# BBB_CNC.net
KiCad netlist of a schematic drawn in EAGLE
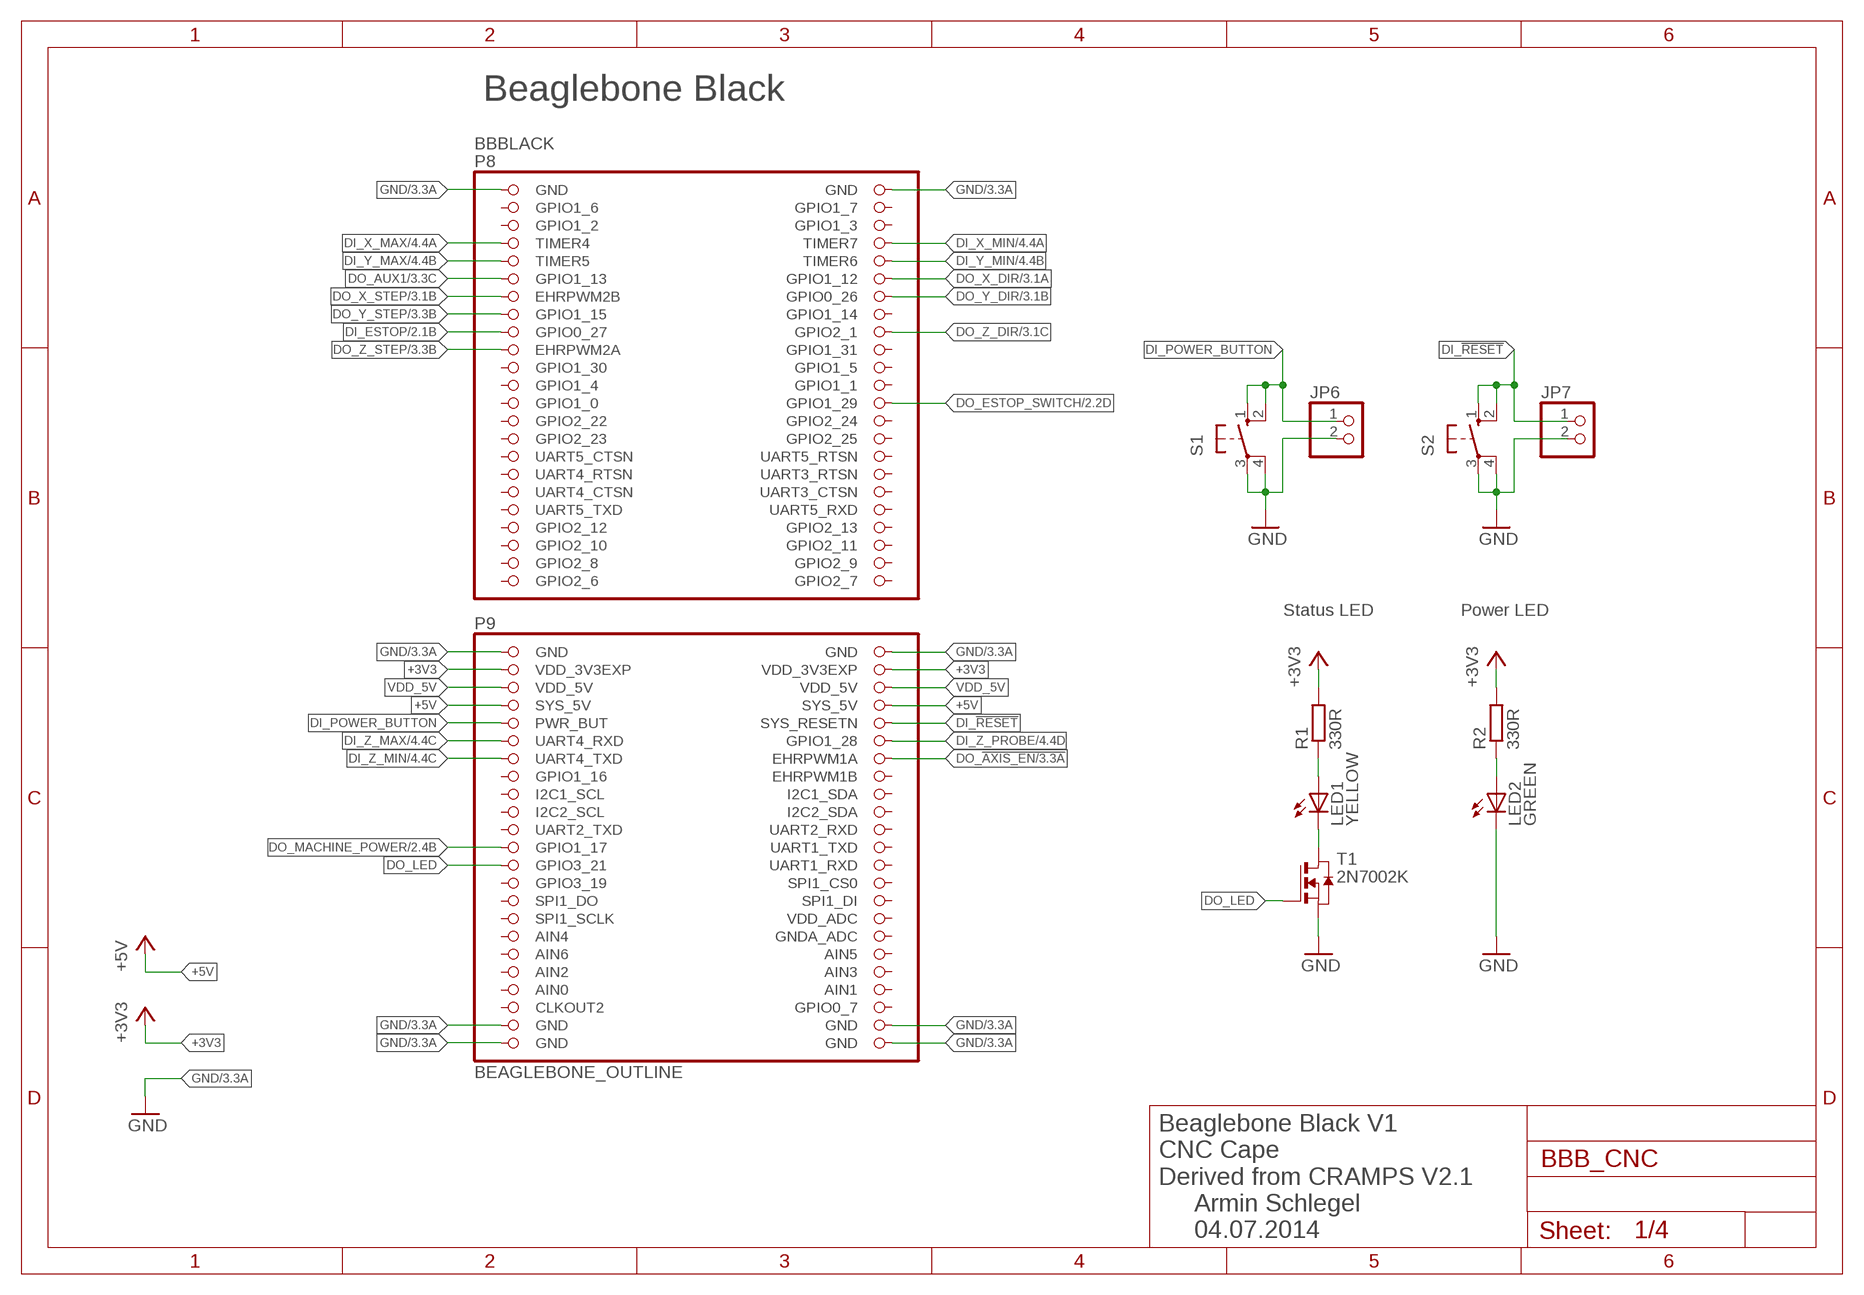
[diagram p0: schematic, sheet 1]
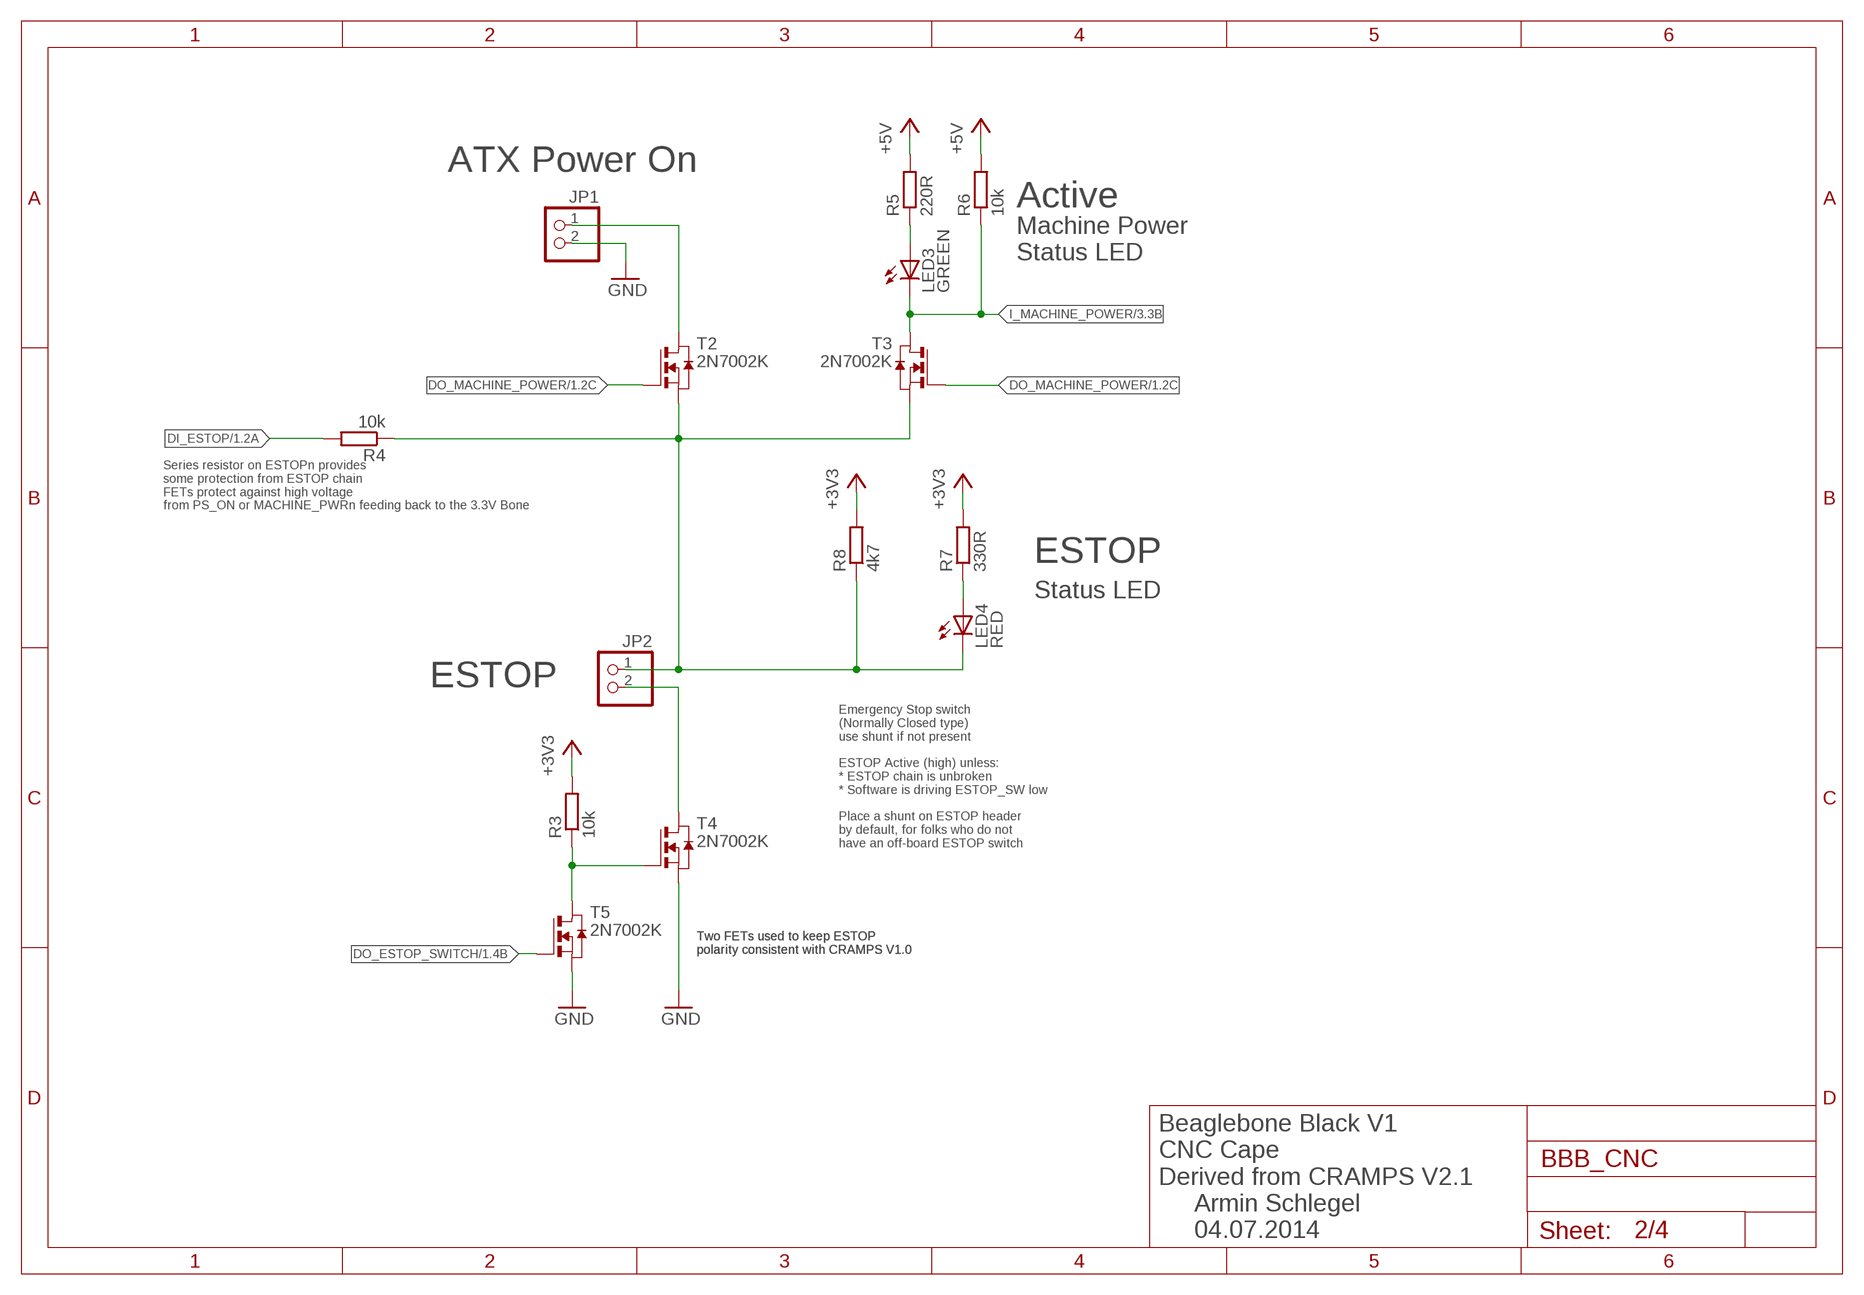
[diagram p1: schematic, sheet 2]
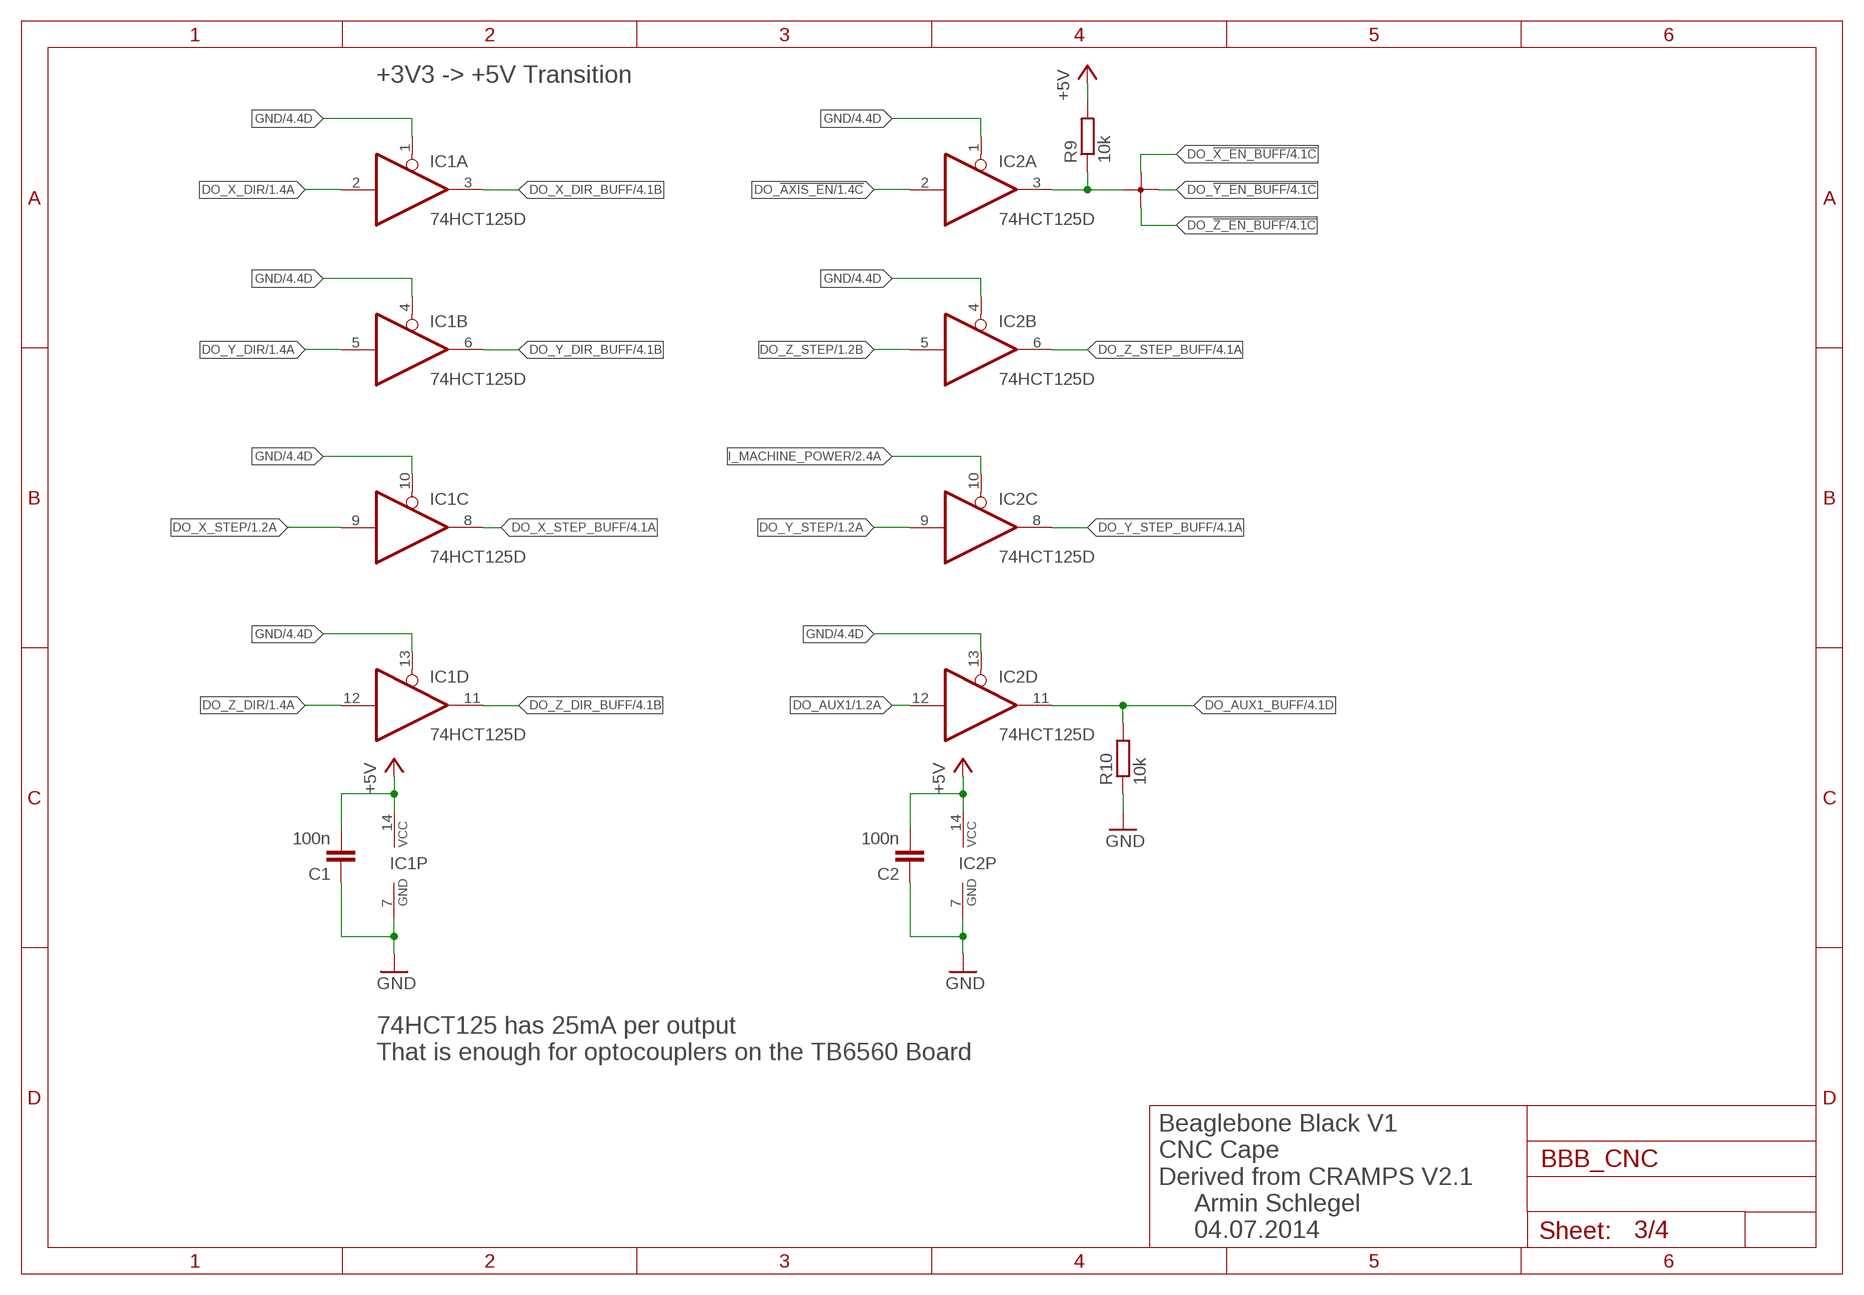
[diagram p2: schematic, sheet 3]
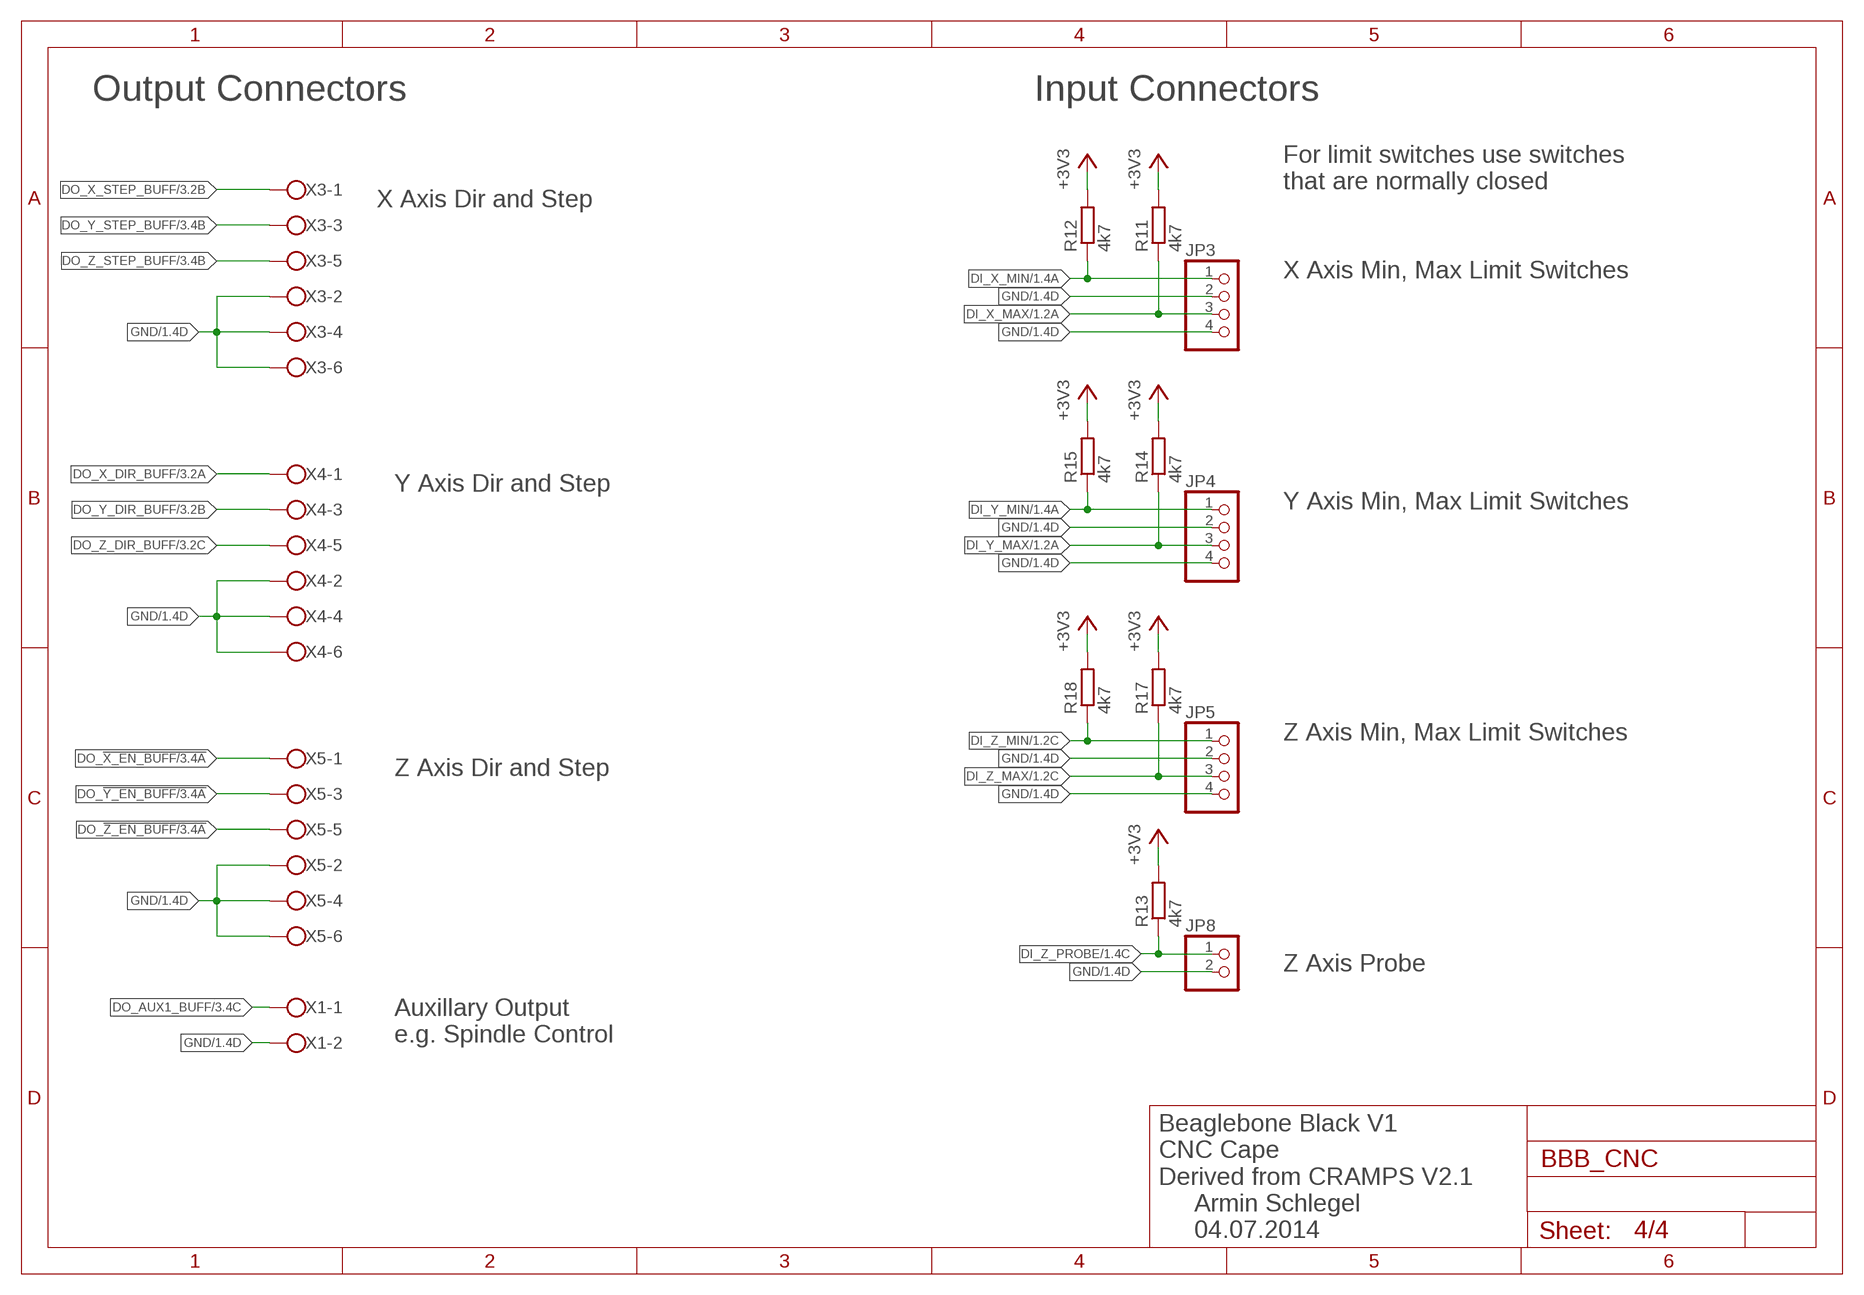
[diagram p3: schematic, sheet 4]

(export (version "E")
  (design (tool "Eeschema 10.0.6"))
  (components
    (comp (ref "JP1")
      (value "PINHD-1X2")
      (footprint "eagle-import:1X02")
      (libsource (lib "eagle-import") (part "PINHD-1X2"))
    )
    (comp (ref "JP2")
      (value "PINHD-1X2")
      (footprint "eagle-import:1X02")
      (libsource (lib "eagle-import") (part "PINHD-1X2"))
    )
    (comp (ref "LED3")
      (value "GREEN")
      (footprint "eagle-import:SML0805")
      (libsource (lib "eagle-import") (part "LEDSML0805"))
    )
    (comp (ref "LED4")
      (value "RED")
      (footprint "eagle-import:SML0805")
      (libsource (lib "eagle-import") (part "LEDSML0805"))
    )
    (comp (ref "R3")
      (value "10k")
      (footprint "eagle-import:R0603")
      (libsource (lib "eagle-import") (part "R-EU_R0603"))
    )
    (comp (ref "R4")
      (value "10k")
      (footprint "eagle-import:R0603")
      (libsource (lib "eagle-import") (part "R-EU_R0603"))
    )
    (comp (ref "R5")
      (value "220R")
      (footprint "eagle-import:R0603")
      (libsource (lib "eagle-import") (part "R-EU_R0603"))
    )
    (comp (ref "R6")
      (value "10k")
      (footprint "eagle-import:R0603")
      (libsource (lib "eagle-import") (part "R-EU_R0603"))
    )
    (comp (ref "R7")
      (value "330R")
      (footprint "eagle-import:R0603")
      (libsource (lib "eagle-import") (part "R-EU_R0603"))
    )
    (comp (ref "R8")
      (value "4k7")
      (footprint "eagle-import:R0603")
      (libsource (lib "eagle-import") (part "R-EU_R0603"))
    )
    (comp (ref "T2")
      (value "2N7002K")
      (footprint "eagle-import:SOT-23")
      (libsource (lib "eagle-import") (part "NMOSSOT23"))
    )
    (comp (ref "T3")
      (value "2N7002K")
      (footprint "eagle-import:SOT-23")
      (libsource (lib "eagle-import") (part "NMOSSOT23"))
    )
    (comp (ref "T4")
      (value "2N7002K")
      (footprint "eagle-import:SOT-23")
      (libsource (lib "eagle-import") (part "NMOSSOT23"))
    )
    (comp (ref "T5")
      (value "2N7002K")
      (footprint "eagle-import:SOT-23")
      (libsource (lib "eagle-import") (part "NMOSSOT23"))
    )
    (comp (ref "JP3")
      (value "PINHD-1X4")
      (footprint "eagle-import:1X04")
      (libsource (lib "eagle-import") (part "PINHD-1X4"))
    )
    (comp (ref "JP4")
      (value "PINHD-1X4")
      (footprint "eagle-import:1X04")
      (libsource (lib "eagle-import") (part "PINHD-1X4"))
    )
    (comp (ref "JP5")
      (value "PINHD-1X4")
      (footprint "eagle-import:1X04")
      (libsource (lib "eagle-import") (part "PINHD-1X4"))
    )
    (comp (ref "JP8")
      (value "PINHD-1X2")
      (footprint "eagle-import:1X02")
      (libsource (lib "eagle-import") (part "PINHD-1X2"))
    )
    (comp (ref "R11")
      (value "4k7")
      (footprint "eagle-import:R0603")
      (libsource (lib "eagle-import") (part "R-EU_R0603"))
    )
    (comp (ref "R12")
      (value "4k7")
      (footprint "eagle-import:R0603")
      (libsource (lib "eagle-import") (part "R-EU_R0603"))
    )
    (comp (ref "R13")
      (value "4k7")
      (footprint "eagle-import:R0603")
      (libsource (lib "eagle-import") (part "R-EU_R0603"))
    )
    (comp (ref "R14")
      (value "4k7")
      (footprint "eagle-import:R0603")
      (libsource (lib "eagle-import") (part "R-EU_R0603"))
    )
    (comp (ref "R15")
      (value "4k7")
      (footprint "eagle-import:R0603")
      (libsource (lib "eagle-import") (part "R-EU_R0603"))
    )
    (comp (ref "R17")
      (value "4k7")
      (footprint "eagle-import:R0603")
      (libsource (lib "eagle-import") (part "R-EU_R0603"))
    )
    (comp (ref "R18")
      (value "4k7")
      (footprint "eagle-import:R0603")
      (libsource (lib "eagle-import") (part "R-EU_R0603"))
    )
    (comp (ref "X1")
      (value "W237-102")
      (footprint "eagle-import:W237-102")
      (fields (field (name "MPN") "237-102"))
      (libsource (lib "eagle-import") (part "W237-102"))
    )
    (comp (ref "X3")
      (value "W237-136")
      (footprint "eagle-import:W237-136")
      (fields (field (name "MPN") "237-136"))
      (libsource (lib "eagle-import") (part "W237-136"))
    )
    (comp (ref "X4")
      (value "W237-136")
      (footprint "eagle-import:W237-136")
      (fields (field (name "MPN") "237-136"))
      (libsource (lib "eagle-import") (part "W237-136"))
    )
    (comp (ref "X5")
      (value "W237-136")
      (footprint "eagle-import:W237-136")
      (fields (field (name "MPN") "237-136"))
      (libsource (lib "eagle-import") (part "W237-136"))
    )
    (comp (ref "BBBLACK")
      (value "BEAGLEBONE_OUTLINE")
      (footprint "eagle-import:BEAGLEBONE_SHIELD")
      (libsource (lib "eagle-import") (part "BEAGLEBONE_OUTLINE"))
    )
    (comp (ref "JP6")
      (value "PINHD-1X2")
      (footprint "eagle-import:1X02")
      (libsource (lib "eagle-import") (part "PINHD-1X2"))
    )
    (comp (ref "JP7")
      (value "PINHD-1X2")
      (footprint "eagle-import:1X02")
      (libsource (lib "eagle-import") (part "PINHD-1X2"))
    )
    (comp (ref "LED1")
      (value "YELLOW")
      (footprint "eagle-import:SML0805")
      (libsource (lib "eagle-import") (part "LEDSML0805"))
    )
    (comp (ref "LED2")
      (value "GREEN")
      (footprint "eagle-import:SML0805")
      (libsource (lib "eagle-import") (part "LEDSML0805"))
    )
    (comp (ref "R1")
      (value "330R")
      (footprint "eagle-import:R0603")
      (libsource (lib "eagle-import") (part "R-EU_R0603"))
    )
    (comp (ref "R2")
      (value "330R")
      (footprint "eagle-import:R0603")
      (libsource (lib "eagle-import") (part "R-EU_R0603"))
    )
    (comp (ref "S1")
      (value "10-XX")
      (footprint "eagle-import:B3F-10XX")
      (fields (field (name "MPN") "B3F-1000"))
      (libsource (lib "eagle-import") (part "10-XX"))
    )
    (comp (ref "S2")
      (value "10-XX")
      (footprint "eagle-import:B3F-10XX")
      (fields (field (name "MPN") "B3F-1000"))
      (libsource (lib "eagle-import") (part "10-XX"))
    )
    (comp (ref "T1")
      (value "2N7002K")
      (footprint "eagle-import:SOT-23")
      (libsource (lib "eagle-import") (part "NMOSSOT23"))
    )
    (comp (ref "C1")
      (value "100n")
      (footprint "eagle-import:C0603K")
      (libsource (lib "eagle-import") (part "C-EUC0603K"))
    )
    (comp (ref "C2")
      (value "100n")
      (footprint "eagle-import:C0603K")
      (libsource (lib "eagle-import") (part "C-EUC0603K"))
    )
    (comp (ref "IC1")
      (value "74HCT125D")
      (footprint "eagle-import:SO14")
      (libsource (lib "eagle-import") (part "74125DHCT"))
    )
    (comp (ref "IC2")
      (value "74HCT125D")
      (footprint "eagle-import:SO14")
      (libsource (lib "eagle-import") (part "74125DHCT"))
    )
    (comp (ref "R9")
      (value "10k")
      (footprint "eagle-import:R0603")
      (libsource (lib "eagle-import") (part "R-EU_R0603"))
    )
    (comp (ref "R10")
      (value "10k")
      (footprint "eagle-import:R0603")
      (libsource (lib "eagle-import") (part "R-EU_R0603"))
    )
    (comp (ref "SP1")
      (value "SP4")
      (footprint "eagle-import:SP4")
      (libsource (lib "eagle-import") (part "SP4"))
    )
  )
  (nets
    (net (code "1") (name "+3V3") (class "Default")
      (node (ref "BBBLACK") (pin "49") (pinfunction "VDD_3V3EXP_49") (pintype "power_in"))
      (node (ref "BBBLACK") (pin "50") (pinfunction "VDD_3V3EXP_50") (pintype "power_in"))
      (node (ref "R1") (pin "2") (pinfunction "2_2") (pintype "passive"))
      (node (ref "R11") (pin "2") (pinfunction "2_2") (pintype "passive"))
      (node (ref "R12") (pin "2") (pinfunction "2_2") (pintype "passive"))
      (node (ref "R13") (pin "2") (pinfunction "2_2") (pintype "passive"))
      (node (ref "R14") (pin "2") (pinfunction "2_2") (pintype "passive"))
      (node (ref "R15") (pin "2") (pinfunction "2_2") (pintype "passive"))
      (node (ref "R17") (pin "2") (pinfunction "2_2") (pintype "passive"))
      (node (ref "R18") (pin "2") (pinfunction "2_2") (pintype "passive"))
      (node (ref "R2") (pin "2") (pinfunction "2_2") (pintype "passive"))
      (node (ref "R3") (pin "2") (pinfunction "2_2") (pintype "passive"))
      (node (ref "R7") (pin "2") (pinfunction "2_2") (pintype "passive"))
      (node (ref "R8") (pin "2") (pinfunction "2_2") (pintype "passive"))
    )
    (net (code "2") (name "+5V") (class "Default")
      (node (ref "BBBLACK") (pin "53") (pinfunction "SYS_5V_53") (pintype "power_in"))
      (node (ref "BBBLACK") (pin "54") (pinfunction "SYS_5V_54") (pintype "passive"))
      (node (ref "C1") (pin "2") (pinfunction "2_2") (pintype "passive"))
      (node (ref "C2") (pin "2") (pinfunction "2_2") (pintype "passive"))
      (node (ref "IC1") (pin "14") (pinfunction "VCC_14") (pintype "power_in"))
      (node (ref "IC2") (pin "14") (pinfunction "VCC_14") (pintype "power_in"))
      (node (ref "R5") (pin "2") (pinfunction "2_2") (pintype "passive"))
      (node (ref "R6") (pin "2") (pinfunction "2_2") (pintype "passive"))
      (node (ref "R9") (pin "2") (pinfunction "2_2") (pintype "passive"))
    )
    (net (code "3") (name "AIN0") (class "Default")
      (node (ref "BBBLACK") (pin "85") (pinfunction "AIN0_85") (pintype "power_in"))
    )
    (net (code "4") (name "DI_ESTOP") (class "Default")
      (node (ref "BBBLACK") (pin "17") (pinfunction "GPIO0_27_17") (pintype "passive"))
      (node (ref "R4") (pin "2") (pinfunction "2_2") (pintype "passive"))
    )
    (net (code "5") (name "DI_POWER_BUTTON") (class "Default")
      (node (ref "BBBLACK") (pin "55") (pinfunction "PWR_BUT_55") (pintype "passive"))
      (node (ref "JP6") (pin "1") (pinfunction "1_1") (pintype "passive"))
      (node (ref "S1") (pin "1") (pinfunction "S_1") (pintype "passive"))
      (node (ref "S1") (pin "2") (pinfunction "S1_2") (pintype "passive"))
    )
    (net (code "6") (name "DI_X_MAX") (class "Default")
      (node (ref "BBBLACK") (pin "7") (pinfunction "TIMER4_7") (pintype "passive"))
      (node (ref "JP3") (pin "3") (pinfunction "3_3") (pintype "passive"))
      (node (ref "R11") (pin "1") (pinfunction "1_1") (pintype "passive"))
    )
    (net (code "7") (name "DI_X_MIN") (class "Default")
      (node (ref "BBBLACK") (pin "8") (pinfunction "TIMER7_8") (pintype "passive"))
      (node (ref "JP3") (pin "1") (pinfunction "1_1") (pintype "passive"))
      (node (ref "R12") (pin "1") (pinfunction "1_1") (pintype "passive"))
    )
    (net (code "8") (name "DI_Y_MAX") (class "Default")
      (node (ref "BBBLACK") (pin "9") (pinfunction "TIMER5_9") (pintype "passive"))
      (node (ref "JP4") (pin "3") (pinfunction "3_3") (pintype "passive"))
      (node (ref "R14") (pin "1") (pinfunction "1_1") (pintype "passive"))
    )
    (net (code "9") (name "DI_Y_MIN") (class "Default")
      (node (ref "BBBLACK") (pin "10") (pinfunction "TIMER6_10") (pintype "passive"))
      (node (ref "JP4") (pin "1") (pinfunction "1_1") (pintype "passive"))
      (node (ref "R15") (pin "1") (pinfunction "1_1") (pintype "passive"))
    )
    (net (code "10") (name "DI_Z_MAX") (class "Default")
      (node (ref "BBBLACK") (pin "57") (pinfunction "UART4_RXD_57") (pintype "passive"))
      (node (ref "JP5") (pin "3") (pinfunction "3_3") (pintype "passive"))
      (node (ref "R17") (pin "1") (pinfunction "1_1") (pintype "passive"))
    )
    (net (code "11") (name "DI_Z_MIN") (class "Default")
      (node (ref "BBBLACK") (pin "59") (pinfunction "UART4_TXD_59") (pintype "passive"))
      (node (ref "JP5") (pin "1") (pinfunction "1_1") (pintype "passive"))
      (node (ref "R18") (pin "1") (pinfunction "1_1") (pintype "passive"))
    )
    (net (code "12") (name "DI_Z_PROBE") (class "Default")
      (node (ref "BBBLACK") (pin "58") (pinfunction "GPIO1_28_58") (pintype "passive"))
      (node (ref "JP8") (pin "1") (pinfunction "1_1") (pintype "passive"))
      (node (ref "R13") (pin "1") (pinfunction "1_1") (pintype "passive"))
    )
    (net (code "13") (name "DI_~{RESET}") (class "Default")
      (node (ref "BBBLACK") (pin "56") (pinfunction "SYS_RESETN_56") (pintype "passive"))
      (node (ref "JP7") (pin "1") (pinfunction "1_1") (pintype "passive"))
      (node (ref "S2") (pin "1") (pinfunction "S_1") (pintype "passive"))
      (node (ref "S2") (pin "2") (pinfunction "S1_2") (pintype "passive"))
    )
    (net (code "14") (name "DO_AUX1") (class "Default")
      (node (ref "BBBLACK") (pin "11") (pinfunction "GPIO1_13_11") (pintype "passive"))
      (node (ref "IC2") (pin "12") (pinfunction "I_12") (pintype "input"))
    )
    (net (code "15") (name "DO_AUX1_BUFF") (class "Default")
      (node (ref "IC2") (pin "11") (pinfunction "O_11") (pintype "tri_state"))
      (node (ref "R10") (pin "2") (pinfunction "2_2") (pintype "passive"))
      (node (ref "X1") (pin "1") (pinfunction "KL_1") (pintype "passive"))
    )
    (net (code "16") (name "DO_ESTOP_SWITCH") (class "Default")
      (node (ref "BBBLACK") (pin "26") (pinfunction "GPIO1_29_26") (pintype "passive"))
      (node (ref "T5") (pin "3") (pinfunction "G_3") (pintype "passive"))
    )
    (net (code "17") (name "DO_LED") (class "Default")
      (node (ref "BBBLACK") (pin "71") (pinfunction "GPIO3_21_71") (pintype "passive"))
      (node (ref "T1") (pin "3") (pinfunction "G_3") (pintype "passive"))
    )
    (net (code "18") (name "DO_MACHINE_POWER") (class "Default")
      (node (ref "BBBLACK") (pin "69") (pinfunction "GPIO1_17_69") (pintype "passive"))
      (node (ref "T2") (pin "3") (pinfunction "G_3") (pintype "passive"))
      (node (ref "T3") (pin "3") (pinfunction "G_3") (pintype "passive"))
    )
    (net (code "19") (name "DO_X_DIR") (class "Default")
      (node (ref "BBBLACK") (pin "12") (pinfunction "GPIO1_12_12") (pintype "passive"))
      (node (ref "IC1") (pin "2") (pinfunction "I_2") (pintype "input"))
    )
    (net (code "20") (name "DO_X_DIR_BUFF") (class "Default")
      (node (ref "IC1") (pin "3") (pinfunction "O_3") (pintype "tri_state"))
      (node (ref "X4") (pin "1") (pinfunction "KL_1") (pintype "passive"))
    )
    (net (code "21") (name "DO_X_STEP") (class "Default")
      (node (ref "BBBLACK") (pin "13") (pinfunction "EHRPWM2B_13") (pintype "passive"))
      (node (ref "IC1") (pin "9") (pinfunction "I_9") (pintype "input"))
    )
    (net (code "22") (name "DO_X_STEP_BUFF") (class "Default")
      (node (ref "IC1") (pin "8") (pinfunction "O_8") (pintype "tri_state"))
      (node (ref "X3") (pin "1") (pinfunction "KL_1") (pintype "passive"))
    )
    (net (code "23") (name "DO_Y_DIR") (class "Default")
      (node (ref "BBBLACK") (pin "14") (pinfunction "GPIO0_26_14") (pintype "passive"))
      (node (ref "IC1") (pin "5") (pinfunction "I_5") (pintype "input"))
    )
    (net (code "24") (name "DO_Y_DIR_BUFF") (class "Default")
      (node (ref "IC1") (pin "6") (pinfunction "O_6") (pintype "tri_state"))
      (node (ref "X4") (pin "3") (pinfunction "KL_3") (pintype "passive"))
    )
    (net (code "25") (name "DO_Y_STEP") (class "Default")
      (node (ref "BBBLACK") (pin "15") (pinfunction "GPIO1_15_15") (pintype "passive"))
      (node (ref "IC2") (pin "9") (pinfunction "I_9") (pintype "input"))
    )
    (net (code "26") (name "DO_Y_STEP_BUFF") (class "Default")
      (node (ref "IC2") (pin "8") (pinfunction "O_8") (pintype "tri_state"))
      (node (ref "X3") (pin "3") (pinfunction "KL_3") (pintype "passive"))
    )
    (net (code "27") (name "DO_Z_DIR") (class "Default")
      (node (ref "BBBLACK") (pin "18") (pinfunction "GPIO2_1_18") (pintype "passive"))
      (node (ref "IC1") (pin "12") (pinfunction "I_12") (pintype "input"))
    )
    (net (code "28") (name "DO_Z_DIR_BUFF") (class "Default")
      (node (ref "IC1") (pin "11") (pinfunction "O_11") (pintype "tri_state"))
      (node (ref "X4") (pin "5") (pinfunction "KL_5") (pintype "passive"))
    )
    (net (code "29") (name "DO_Z_STEP") (class "Default")
      (node (ref "BBBLACK") (pin "19") (pinfunction "EHRPWM2A_19") (pintype "passive"))
      (node (ref "IC2") (pin "5") (pinfunction "I_5") (pintype "input"))
    )
    (net (code "30") (name "DO_Z_STEP_BUFF") (class "Default")
      (node (ref "IC2") (pin "6") (pinfunction "O_6") (pintype "tri_state"))
      (node (ref "X3") (pin "5") (pinfunction "KL_5") (pintype "passive"))
    )
    (net (code "31") (name "DO_~{AXIS_EN}") (class "Default")
      (node (ref "BBBLACK") (pin "60") (pinfunction "EHRPWM1A_60") (pintype "passive"))
      (node (ref "IC2") (pin "2") (pinfunction "I_2") (pintype "input"))
    )
    (net (code "32") (name "DO_~{X_EN_BUFF}") (class "Default")
      (node (ref "SP1") (pin "P$4") (pinfunction "4_P$4") (pintype "bidirectional"))
      (node (ref "X5") (pin "1") (pinfunction "KL_1") (pintype "passive"))
    )
    (net (code "33") (name "DO_~{Y_EN_BUFF}") (class "Default")
      (node (ref "SP1") (pin "P$2") (pinfunction "2_P$2") (pintype "bidirectional"))
      (node (ref "X5") (pin "3") (pinfunction "KL_3") (pintype "passive"))
    )
    (net (code "34") (name "DO_~{Z_EN_BUFF}") (class "Default")
      (node (ref "SP1") (pin "P$3") (pinfunction "3_P$3") (pintype "bidirectional"))
      (node (ref "X5") (pin "5") (pinfunction "KL_5") (pintype "passive"))
    )
    (net (code "35") (name "GND") (class "Default")
      (node (ref "BBBLACK") (pin "1") (pinfunction "GND_1") (pintype "power_in"))
      (node (ref "BBBLACK") (pin "2") (pinfunction "GND_2") (pintype "power_in"))
      (node (ref "BBBLACK") (pin "47") (pinfunction "GND_47") (pintype "power_in"))
      (node (ref "BBBLACK") (pin "48") (pinfunction "GND_48") (pintype "power_in"))
      (node (ref "BBBLACK") (pin "89") (pinfunction "GND_89") (pintype "power_in"))
      (node (ref "BBBLACK") (pin "90") (pinfunction "GND_90") (pintype "power_in"))
      (node (ref "BBBLACK") (pin "91") (pinfunction "GND_91") (pintype "power_in"))
      (node (ref "BBBLACK") (pin "92") (pinfunction "GND_92") (pintype "power_in"))
      (node (ref "C1") (pin "1") (pinfunction "1_1") (pintype "passive"))
      (node (ref "C2") (pin "1") (pinfunction "1_1") (pintype "passive"))
      (node (ref "IC1") (pin "1") (pinfunction "OE_1") (pintype "input"))
      (node (ref "IC1") (pin "10") (pinfunction "OE_10") (pintype "input"))
      (node (ref "IC1") (pin "13") (pinfunction "OE_13") (pintype "input"))
      (node (ref "IC1") (pin "4") (pinfunction "OE_4") (pintype "input"))
      (node (ref "IC1") (pin "7") (pinfunction "GND_7") (pintype "power_in"))
      (node (ref "IC2") (pin "1") (pinfunction "OE_1") (pintype "input"))
      (node (ref "IC2") (pin "13") (pinfunction "OE_13") (pintype "input"))
      (node (ref "IC2") (pin "4") (pinfunction "OE_4") (pintype "input"))
      (node (ref "IC2") (pin "7") (pinfunction "GND_7") (pintype "power_in"))
      (node (ref "JP1") (pin "2") (pinfunction "2_2") (pintype "passive"))
      (node (ref "JP3") (pin "2") (pinfunction "2_2") (pintype "passive"))
      (node (ref "JP3") (pin "4") (pinfunction "4_4") (pintype "passive"))
      (node (ref "JP4") (pin "2") (pinfunction "2_2") (pintype "passive"))
      (node (ref "JP4") (pin "4") (pinfunction "4_4") (pintype "passive"))
      (node (ref "JP5") (pin "2") (pinfunction "2_2") (pintype "passive"))
      (node (ref "JP5") (pin "4") (pinfunction "4_4") (pintype "passive"))
      (node (ref "JP6") (pin "2") (pinfunction "2_2") (pintype "passive"))
      (node (ref "JP7") (pin "2") (pinfunction "2_2") (pintype "passive"))
      (node (ref "JP8") (pin "2") (pinfunction "2_2") (pintype "passive"))
      (node (ref "LED2") (pin "C") (pinfunction "C_C") (pintype "passive"))
      (node (ref "R10") (pin "1") (pinfunction "1_1") (pintype "passive"))
      (node (ref "S1") (pin "3") (pinfunction "P_3") (pintype "passive"))
      (node (ref "S1") (pin "4") (pinfunction "P1_4") (pintype "passive"))
      (node (ref "S2") (pin "3") (pinfunction "P_3") (pintype "passive"))
      (node (ref "S2") (pin "4") (pinfunction "P1_4") (pintype "passive"))
      (node (ref "T1") (pin "2") (pinfunction "S_2") (pintype "passive"))
      (node (ref "T4") (pin "2") (pinfunction "S_2") (pintype "passive"))
      (node (ref "T5") (pin "2") (pinfunction "S_2") (pintype "passive"))
      (node (ref "X1") (pin "2") (pinfunction "KL_2") (pintype "passive"))
      (node (ref "X3") (pin "2") (pinfunction "KL_2") (pintype "passive"))
      (node (ref "X3") (pin "4") (pinfunction "KL_4") (pintype "passive"))
      (node (ref "X3") (pin "6") (pinfunction "KL_6") (pintype "passive"))
      (node (ref "X4") (pin "2") (pinfunction "KL_2") (pintype "passive"))
      (node (ref "X4") (pin "4") (pinfunction "KL_4") (pintype "passive"))
      (node (ref "X4") (pin "6") (pinfunction "KL_6") (pintype "passive"))
      (node (ref "X5") (pin "2") (pinfunction "KL_2") (pintype "passive"))
      (node (ref "X5") (pin "4") (pinfunction "KL_4") (pintype "passive"))
      (node (ref "X5") (pin "6") (pinfunction "KL_6") (pintype "passive"))
    )
    (net (code "36") (name "I_MACHINE_POWER") (class "Default")
      (node (ref "IC2") (pin "10") (pinfunction "OE_10") (pintype "input"))
      (node (ref "LED3") (pin "C") (pinfunction "C_C") (pintype "passive"))
      (node (ref "R6") (pin "1") (pinfunction "1_1") (pintype "passive"))
      (node (ref "T3") (pin "1") (pinfunction "D_1") (pintype "passive"))
    )
    (net (code "37") (name "Net-(IC2A-O)") (class "Default")
      (node (ref "IC2") (pin "3") (pinfunction "O_3") (pintype "tri_state"))
      (node (ref "R9") (pin "1") (pinfunction "1_1") (pintype "passive"))
      (node (ref "SP1") (pin "P$1") (pinfunction "1_P$1") (pintype "bidirectional"))
    )
    (net (code "38") (name "Net-(LED1-PadA)") (class "Default")
      (node (ref "LED1") (pin "A") (pinfunction "A_A") (pintype "passive"))
      (node (ref "R1") (pin "1") (pinfunction "1_1") (pintype "passive"))
    )
    (net (code "39") (name "Net-(LED2-PadA)") (class "Default")
      (node (ref "LED2") (pin "A") (pinfunction "A_A") (pintype "passive"))
      (node (ref "R2") (pin "1") (pinfunction "1_1") (pintype "passive"))
    )
    (net (code "40") (name "Net-(LED3-PadA)") (class "Default")
      (node (ref "LED3") (pin "A") (pinfunction "A_A") (pintype "passive"))
      (node (ref "R5") (pin "1") (pinfunction "1_1") (pintype "passive"))
    )
    (net (code "41") (name "Net-(LED4-PadA)") (class "Default")
      (node (ref "LED4") (pin "A") (pinfunction "A_A") (pintype "passive"))
      (node (ref "R7") (pin "1") (pinfunction "1_1") (pintype "passive"))
    )
    (net (code "42") (name "Net-(T1-D)") (class "Default")
      (node (ref "LED1") (pin "C") (pinfunction "C_C") (pintype "passive"))
      (node (ref "T1") (pin "1") (pinfunction "D_1") (pintype "passive"))
    )
    (net (code "43") (name "Net-(T2-D)") (class "Default")
      (node (ref "JP1") (pin "1") (pinfunction "1_1") (pintype "passive"))
      (node (ref "T2") (pin "1") (pinfunction "D_1") (pintype "passive"))
    )
    (net (code "44") (name "Net-(T2-S)") (class "Default")
      (node (ref "JP2") (pin "1") (pinfunction "1_1") (pintype "passive"))
      (node (ref "LED4") (pin "C") (pinfunction "C_C") (pintype "passive"))
      (node (ref "R4") (pin "1") (pinfunction "1_1") (pintype "passive"))
      (node (ref "R8") (pin "1") (pinfunction "1_1") (pintype "passive"))
      (node (ref "T2") (pin "2") (pinfunction "S_2") (pintype "passive"))
      (node (ref "T3") (pin "2") (pinfunction "S_2") (pintype "passive"))
    )
    (net (code "45") (name "Net-(T4-D)") (class "Default")
      (node (ref "JP2") (pin "2") (pinfunction "2_2") (pintype "passive"))
      (node (ref "T4") (pin "1") (pinfunction "D_1") (pintype "passive"))
    )
    (net (code "46") (name "Net-(T4-G)") (class "Default")
      (node (ref "R3") (pin "1") (pinfunction "1_1") (pintype "passive"))
      (node (ref "T4") (pin "3") (pinfunction "G_3") (pintype "passive"))
      (node (ref "T5") (pin "1") (pinfunction "D_1") (pintype "passive"))
    )
    (net (code "47") (name "VDD_5V") (class "Default")
      (node (ref "BBBLACK") (pin "51") (pinfunction "VDD_5V_51") (pintype "power_in"))
      (node (ref "BBBLACK") (pin "52") (pinfunction "VDD_5V_52") (pintype "power_in"))
    )
    (net (code "48") (name "unconnected-(BBBLACK-AIN1-Pad86)") (class "Default")
      (node (ref "BBBLACK") (pin "86") (pinfunction "AIN1_86") (pintype "passive"))
    )
    (net (code "49") (name "unconnected-(BBBLACK-AIN2-Pad83)") (class "Default")
      (node (ref "BBBLACK") (pin "83") (pinfunction "AIN2_83") (pintype "passive"))
    )
    (net (code "50") (name "unconnected-(BBBLACK-AIN3-Pad84)") (class "Default")
      (node (ref "BBBLACK") (pin "84") (pinfunction "AIN3_84") (pintype "passive"))
    )
    (net (code "51") (name "unconnected-(BBBLACK-AIN4-Pad79)") (class "Default")
      (node (ref "BBBLACK") (pin "79") (pinfunction "AIN4_79") (pintype "passive"))
    )
    (net (code "52") (name "unconnected-(BBBLACK-AIN5-Pad82)") (class "Default")
      (node (ref "BBBLACK") (pin "82") (pinfunction "AIN5_82") (pintype "passive"))
    )
    (net (code "53") (name "unconnected-(BBBLACK-AIN6-Pad81)") (class "Default")
      (node (ref "BBBLACK") (pin "81") (pinfunction "AIN6_81") (pintype "passive"))
    )
    (net (code "54") (name "unconnected-(BBBLACK-CLKOUT2-Pad87)") (class "Default")
      (node (ref "BBBLACK") (pin "87") (pinfunction "CLKOUT2_87") (pintype "input"))
    )
    (net (code "55") (name "unconnected-(BBBLACK-EHRPWM1B-Pad62)") (class "Default")
      (node (ref "BBBLACK") (pin "62") (pinfunction "EHRPWM1B_62") (pintype "passive"))
    )
    (net (code "56") (name "unconnected-(BBBLACK-GNDA_ADC-Pad80)") (class "Default")
      (node (ref "BBBLACK") (pin "80") (pinfunction "GNDA_ADC_80") (pintype "passive"))
    )
    (net (code "57") (name "unconnected-(BBBLACK-GPIO0_7-Pad88)") (class "Default")
      (node (ref "BBBLACK") (pin "88") (pinfunction "GPIO0_7_88") (pintype "passive"))
    )
    (net (code "58") (name "unconnected-(BBBLACK-GPIO1_0-Pad25)") (class "Default")
      (node (ref "BBBLACK") (pin "25") (pinfunction "GPIO1_0_25") (pintype "passive"))
    )
    (net (code "59") (name "unconnected-(BBBLACK-GPIO1_1-Pad24)") (class "Default")
      (node (ref "BBBLACK") (pin "24") (pinfunction "GPIO1_1_24") (pintype "passive"))
    )
    (net (code "60") (name "unconnected-(BBBLACK-GPIO1_2-Pad5)") (class "Default")
      (node (ref "BBBLACK") (pin "5") (pinfunction "GPIO1_2_5") (pintype "passive"))
    )
    (net (code "61") (name "unconnected-(BBBLACK-GPIO1_3-Pad6)") (class "Default")
      (node (ref "BBBLACK") (pin "6") (pinfunction "GPIO1_3_6") (pintype "passive"))
    )
    (net (code "62") (name "unconnected-(BBBLACK-GPIO1_4-Pad23)") (class "Default")
      (node (ref "BBBLACK") (pin "23") (pinfunction "GPIO1_4_23") (pintype "passive"))
    )
    (net (code "63") (name "unconnected-(BBBLACK-GPIO1_5-Pad22)") (class "Default")
      (node (ref "BBBLACK") (pin "22") (pinfunction "GPIO1_5_22") (pintype "passive"))
    )
    (net (code "64") (name "unconnected-(BBBLACK-GPIO1_6-Pad3)") (class "Default")
      (node (ref "BBBLACK") (pin "3") (pinfunction "GPIO1_6_3") (pintype "passive"))
    )
    (net (code "65") (name "unconnected-(BBBLACK-GPIO1_7-Pad4)") (class "Default")
      (node (ref "BBBLACK") (pin "4") (pinfunction "GPIO1_7_4") (pintype "passive"))
    )
    (net (code "66") (name "unconnected-(BBBLACK-GPIO1_14-Pad16)") (class "Default")
      (node (ref "BBBLACK") (pin "16") (pinfunction "GPIO1_14_16") (pintype "passive"))
    )
    (net (code "67") (name "unconnected-(BBBLACK-GPIO1_16-Pad61)") (class "Default")
      (node (ref "BBBLACK") (pin "61") (pinfunction "GPIO1_16_61") (pintype "passive"))
    )
    (net (code "68") (name "unconnected-(BBBLACK-GPIO1_30-Pad21)") (class "Default")
      (node (ref "BBBLACK") (pin "21") (pinfunction "GPIO1_30_21") (pintype "passive"))
    )
    (net (code "69") (name "unconnected-(BBBLACK-GPIO1_31-Pad20)") (class "Default")
      (node (ref "BBBLACK") (pin "20") (pinfunction "GPIO1_31_20") (pintype "passive"))
    )
    (net (code "70") (name "unconnected-(BBBLACK-GPIO2_6-Pad45)") (class "Default")
      (node (ref "BBBLACK") (pin "45") (pinfunction "GPIO2_6_45") (pintype "passive"))
    )
    (net (code "71") (name "unconnected-(BBBLACK-GPIO2_7-Pad46)") (class "Default")
      (node (ref "BBBLACK") (pin "46") (pinfunction "GPIO2_7_46") (pintype "passive"))
    )
    (net (code "72") (name "unconnected-(BBBLACK-GPIO2_8-Pad43)") (class "Default")
      (node (ref "BBBLACK") (pin "43") (pinfunction "GPIO2_8_43") (pintype "passive"))
    )
    (net (code "73") (name "unconnected-(BBBLACK-GPIO2_9-Pad44)") (class "Default")
      (node (ref "BBBLACK") (pin "44") (pinfunction "GPIO2_9_44") (pintype "passive"))
    )
    (net (code "74") (name "unconnected-(BBBLACK-GPIO2_10-Pad41)") (class "Default")
      (node (ref "BBBLACK") (pin "41") (pinfunction "GPIO2_10_41") (pintype "passive"))
    )
    (net (code "75") (name "unconnected-(BBBLACK-GPIO2_11-Pad42)") (class "Default")
      (node (ref "BBBLACK") (pin "42") (pinfunction "GPIO2_11_42") (pintype "passive"))
    )
    (net (code "76") (name "unconnected-(BBBLACK-GPIO2_12-Pad39)") (class "Default")
      (node (ref "BBBLACK") (pin "39") (pinfunction "GPIO2_12_39") (pintype "passive"))
    )
    (net (code "77") (name "unconnected-(BBBLACK-GPIO2_13-Pad40)") (class "Default")
      (node (ref "BBBLACK") (pin "40") (pinfunction "GPIO2_13_40") (pintype "passive"))
    )
    (net (code "78") (name "unconnected-(BBBLACK-GPIO2_22-Pad27)") (class "Default")
      (node (ref "BBBLACK") (pin "27") (pinfunction "GPIO2_22_27") (pintype "passive"))
    )
    (net (code "79") (name "unconnected-(BBBLACK-GPIO2_23-Pad29)") (class "Default")
      (node (ref "BBBLACK") (pin "29") (pinfunction "GPIO2_23_29") (pintype "passive"))
    )
    (net (code "80") (name "unconnected-(BBBLACK-GPIO2_24-Pad28)") (class "Default")
      (node (ref "BBBLACK") (pin "28") (pinfunction "GPIO2_24_28") (pintype "passive"))
    )
    (net (code "81") (name "unconnected-(BBBLACK-GPIO2_25-Pad30)") (class "Default")
      (node (ref "BBBLACK") (pin "30") (pinfunction "GPIO2_25_30") (pintype "passive"))
    )
    (net (code "82") (name "unconnected-(BBBLACK-GPIO3_19-Pad73)") (class "Default")
      (node (ref "BBBLACK") (pin "73") (pinfunction "GPIO3_19_73") (pintype "passive"))
    )
    (net (code "83") (name "unconnected-(BBBLACK-I2C1_SCL-Pad63)") (class "Default")
      (node (ref "BBBLACK") (pin "63") (pinfunction "I2C1_SCL_63") (pintype "passive"))
    )
    (net (code "84") (name "unconnected-(BBBLACK-I2C1_SDA-Pad64)") (class "Default")
      (node (ref "BBBLACK") (pin "64") (pinfunction "I2C1_SDA_64") (pintype "passive"))
    )
    (net (code "85") (name "unconnected-(BBBLACK-I2C2_SCL-Pad65)") (class "Default")
      (node (ref "BBBLACK") (pin "65") (pinfunction "I2C2_SCL_65") (pintype "passive"))
    )
    (net (code "86") (name "unconnected-(BBBLACK-I2C2_SDA-Pad66)") (class "Default")
      (node (ref "BBBLACK") (pin "66") (pinfunction "I2C2_SDA_66") (pintype "passive"))
    )
    (net (code "87") (name "unconnected-(BBBLACK-SPI1_CS0-Pad74)") (class "Default")
      (node (ref "BBBLACK") (pin "74") (pinfunction "SPI1_CS0_74") (pintype "passive"))
    )
    (net (code "88") (name "unconnected-(BBBLACK-SPI1_DI-Pad76)") (class "Default")
      (node (ref "BBBLACK") (pin "76") (pinfunction "SPI1_DI_76") (pintype "passive"))
    )
    (net (code "89") (name "unconnected-(BBBLACK-SPI1_DO-Pad75)") (class "Default")
      (node (ref "BBBLACK") (pin "75") (pinfunction "SPI1_DO_75") (pintype "passive"))
    )
    (net (code "90") (name "unconnected-(BBBLACK-SPI1_SCLK-Pad77)") (class "Default")
      (node (ref "BBBLACK") (pin "77") (pinfunction "SPI1_SCLK_77") (pintype "passive"))
    )
    (net (code "91") (name "unconnected-(BBBLACK-UART1_RXD-Pad72)") (class "Default")
      (node (ref "BBBLACK") (pin "72") (pinfunction "UART1_RXD_72") (pintype "passive"))
    )
    (net (code "92") (name "unconnected-(BBBLACK-UART1_TXD-Pad70)") (class "Default")
      (node (ref "BBBLACK") (pin "70") (pinfunction "UART1_TXD_70") (pintype "passive"))
    )
    (net (code "93") (name "unconnected-(BBBLACK-UART2_RXD-Pad68)") (class "Default")
      (node (ref "BBBLACK") (pin "68") (pinfunction "UART2_RXD_68") (pintype "passive"))
    )
    (net (code "94") (name "unconnected-(BBBLACK-UART2_TXD-Pad67)") (class "Default")
      (node (ref "BBBLACK") (pin "67") (pinfunction "UART2_TXD_67") (pintype "passive"))
    )
    (net (code "95") (name "unconnected-(BBBLACK-UART3_CTSN-Pad36)") (class "Default")
      (node (ref "BBBLACK") (pin "36") (pinfunction "UART3_CTSN_36") (pintype "passive"))
    )
    (net (code "96") (name "unconnected-(BBBLACK-UART3_RTSN-Pad34)") (class "Default")
      (node (ref "BBBLACK") (pin "34") (pinfunction "UART3_RTSN_34") (pintype "passive"))
    )
    (net (code "97") (name "unconnected-(BBBLACK-UART4_CTSN-Pad35)") (class "Default")
      (node (ref "BBBLACK") (pin "35") (pinfunction "UART4_CTSN_35") (pintype "passive"))
    )
    (net (code "98") (name "unconnected-(BBBLACK-UART4_RTSN-Pad33)") (class "Default")
      (node (ref "BBBLACK") (pin "33") (pinfunction "UART4_RTSN_33") (pintype "passive"))
    )
    (net (code "99") (name "unconnected-(BBBLACK-UART5_CTSN-Pad31)") (class "Default")
      (node (ref "BBBLACK") (pin "31") (pinfunction "UART5_CTSN_31") (pintype "passive"))
    )
    (net (code "100") (name "unconnected-(BBBLACK-UART5_RTSN-Pad32)") (class "Default")
      (node (ref "BBBLACK") (pin "32") (pinfunction "UART5_RTSN_32") (pintype "passive"))
    )
    (net (code "101") (name "unconnected-(BBBLACK-UART5_RXD-Pad38)") (class "Default")
      (node (ref "BBBLACK") (pin "38") (pinfunction "UART5_RXD_38") (pintype "passive"))
    )
    (net (code "102") (name "unconnected-(BBBLACK-UART5_TXD-Pad37)") (class "Default")
      (node (ref "BBBLACK") (pin "37") (pinfunction "UART5_TXD_37") (pintype "passive"))
    )
    (net (code "103") (name "unconnected-(BBBLACK-VDD_ADC-Pad78)") (class "Default")
      (node (ref "BBBLACK") (pin "78") (pinfunction "VDD_ADC_78") (pintype "passive"))
    )
  )
)
